# RGB_HDMI.net
KiCad netlist of a schematic drawn in EAGLE
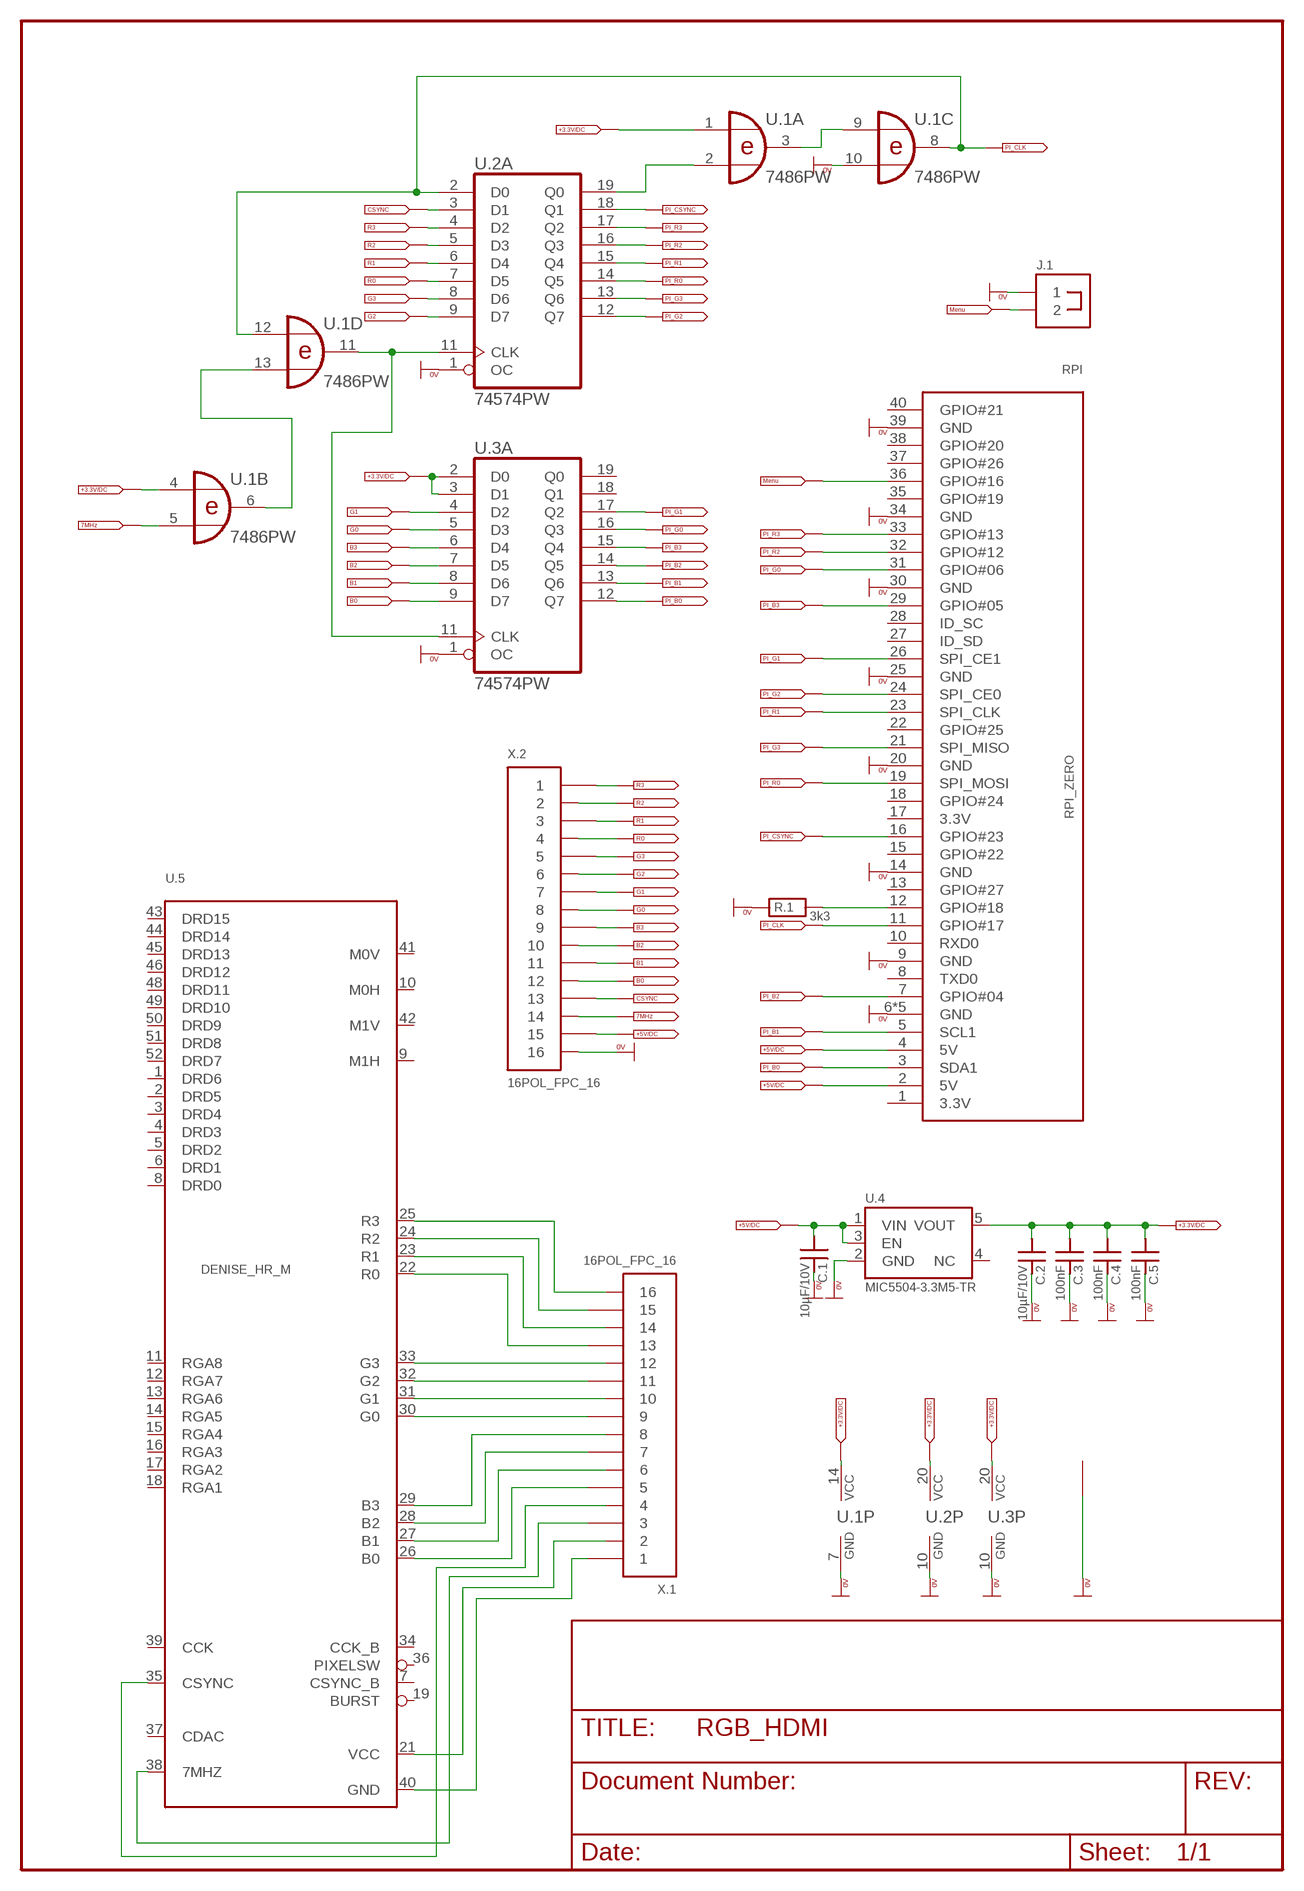
[diagram p0: schematic, sheet 1]

(export (version "E")
  (design (tool "Eeschema 10.0.6"))
  (components
    (comp (ref "C.1")
      (value "10µF/10V")
      (footprint "eagle-import:0805")
      (libsource (lib "eagle-import") (part "CAPACITOR_SMD_0805"))
    )
    (comp (ref "C.2")
      (value "10µF/10V")
      (footprint "eagle-import:0805")
      (libsource (lib "eagle-import") (part "CAPACITOR_SMD_0805"))
    )
    (comp (ref "C.3")
      (value "100nF")
      (footprint "eagle-import:0805")
      (libsource (lib "eagle-import") (part "CAPACITOR_SMD_0805"))
    )
    (comp (ref "C.4")
      (value "100nF")
      (footprint "eagle-import:0805")
      (libsource (lib "eagle-import") (part "CAPACITOR_SMD_0805"))
    )
    (comp (ref "C.5")
      (value "100nF")
      (footprint "eagle-import:0805")
      (libsource (lib "eagle-import") (part "CAPACITOR_SMD_0805"))
    )
    (comp (ref "J.1")
      (value "2POLIG_1REIHIG")
      (footprint "eagle-import:2POLIG_1REIHIG")
      (libsource (lib "eagle-import") (part "2POLIG_1REIHIG"))
    )
    (comp (ref "K.1")
      (value "PAD_1,0SQ")
      (footprint "eagle-import:1,0SQ")
      (libsource (lib "eagle-import") (part "PAD_1,0SQ"))
    )
    (comp (ref "R.1")
      (value "3k3")
      (footprint "eagle-import:0805")
      (libsource (lib "eagle-import") (part "RESISTOR_SMD_0805"))
    )
    (comp (ref "RPI")
      (value "RPI_ZERO")
      (footprint "eagle-import:RPI_ZERO_FULL")
      (libsource (lib "eagle-import") (part "RPI_ZERO"))
    )
    (comp (ref "U.1")
      (value "7486PW")
      (footprint "eagle-import:TSSOP14")
      (libsource (lib "eagle-import") (part "7486PW"))
    )
    (comp (ref "U.2")
      (value "74574PW")
      (footprint "eagle-import:TSSOP20")
      (libsource (lib "eagle-import") (part "74574PW"))
    )
    (comp (ref "U.3")
      (value "74574PW")
      (footprint "eagle-import:TSSOP20")
      (libsource (lib "eagle-import") (part "74574PW"))
    )
    (comp (ref "U.4")
      (value "MIC5504-3.3M5-TR")
      (footprint "eagle-import:SOT23-5")
      (libsource (lib "eagle-import") (part "TLV755P"))
    )
    (comp (ref "U.5")
      (value "DENISE_HR_M")
      (footprint "eagle-import:PLCC_52_MIRROR")
      (libsource (lib "eagle-import") (part "DENISE_HR_M"))
    )
    (comp (ref "X.1")
      (value "16POL_FPC_16")
      (footprint "eagle-import:MOLEX_FPC_16")
      (libsource (lib "eagle-import") (part "16POL_FPC_16"))
    )
    (comp (ref "X.2")
      (value "16POL_FPC_16")
      (footprint "eagle-import:MOLEX_FPC_16")
      (libsource (lib "eagle-import") (part "16POL_FPC_16"))
    )
  )
  (nets
    (net (code "1") (name "+3.3V-IN") (class "Default")
      (node (ref "C.2") (pin "1") (pinfunction "1_1") (pintype "passive"))
      (node (ref "C.3") (pin "1") (pinfunction "1_1") (pintype "passive"))
      (node (ref "C.4") (pin "1") (pinfunction "1_1") (pintype "passive"))
      (node (ref "C.5") (pin "1") (pinfunction "1_1") (pintype "passive"))
      (node (ref "U.1") (pin "1") (pinfunction "I0_1") (pintype "input"))
      (node (ref "U.1") (pin "14") (pinfunction "VCC_14") (pintype "power_in"))
      (node (ref "U.1") (pin "4") (pinfunction "I0_4") (pintype "input"))
      (node (ref "U.2") (pin "20") (pinfunction "VCC_20") (pintype "power_in"))
      (node (ref "U.3") (pin "2") (pinfunction "D0_2") (pintype "input"))
      (node (ref "U.3") (pin "20") (pinfunction "VCC_20") (pintype "power_in"))
      (node (ref "U.3") (pin "3") (pinfunction "D1_3") (pintype "input"))
      (node (ref "U.4") (pin "5") (pinfunction "VOUT_5") (pintype "bidirectional"))
    )
    (net (code "2") (name "+5V-IN") (class "Default")
      (node (ref "C.1") (pin "1") (pinfunction "1_1") (pintype "passive"))
      (node (ref "RPI") (pin "2") (pinfunction "5V_2") (pintype "bidirectional"))
      (node (ref "RPI") (pin "4") (pinfunction "5V_4") (pintype "bidirectional"))
      (node (ref "U.4") (pin "1") (pinfunction "VIN_1") (pintype "bidirectional"))
      (node (ref "U.4") (pin "3") (pinfunction "EN_3") (pintype "bidirectional"))
      (node (ref "X.2") (pin "15") (pinfunction "15_15") (pintype "passive"))
    )
    (net (code "3") (name "0V") (class "Default")
      (node (ref "C.1") (pin "2") (pinfunction "2_2") (pintype "passive"))
      (node (ref "C.2") (pin "2") (pinfunction "2_2") (pintype "passive"))
      (node (ref "C.3") (pin "2") (pinfunction "2_2") (pintype "passive"))
      (node (ref "C.4") (pin "2") (pinfunction "2_2") (pintype "passive"))
      (node (ref "C.5") (pin "2") (pinfunction "2_2") (pintype "passive"))
      (node (ref "J.1") (pin "1") (pinfunction "1_1") (pintype "passive"))
      (node (ref "K.1") (pin "P$1") (pinfunction "P$1_P$1") (pintype "bidirectional"))
      (node (ref "R.1") (pin "1") (pinfunction "1_1") (pintype "passive"))
      (node (ref "RPI") (pin "14") (pinfunction "GND_14") (pintype "bidirectional"))
      (node (ref "RPI") (pin "20") (pinfunction "GND_20") (pintype "bidirectional"))
      (node (ref "RPI") (pin "25") (pinfunction "GND_25") (pintype "bidirectional"))
      (node (ref "RPI") (pin "30") (pinfunction "GND_30") (pintype "bidirectional"))
      (node (ref "RPI") (pin "34") (pinfunction "GND_34") (pintype "bidirectional"))
      (node (ref "RPI") (pin "39") (pinfunction "GND_39") (pintype "bidirectional"))
      (node (ref "RPI") (pin "6") (pinfunction "GND_6") (pintype "bidirectional"))
      (node (ref "RPI") (pin "9") (pinfunction "GND_9") (pintype "bidirectional"))
      (node (ref "RPI") (pin "P$1") (pinfunction "GND_P$1") (pintype "bidirectional"))
      (node (ref "RPI") (pin "P$2") (pinfunction "GND_P$2") (pintype "bidirectional"))
      (node (ref "RPI") (pin "P$3") (pinfunction "GND_P$3") (pintype "bidirectional"))
      (node (ref "RPI") (pin "P$4") (pinfunction "GND_P$4") (pintype "bidirectional"))
      (node (ref "U.1") (pin "10") (pinfunction "I1_10") (pintype "input"))
      (node (ref "U.1") (pin "7") (pinfunction "GND_7") (pintype "power_in"))
      (node (ref "U.2") (pin "1") (pinfunction "OC_1") (pintype "input"))
      (node (ref "U.2") (pin "10") (pinfunction "GND_10") (pintype "power_in"))
      (node (ref "U.3") (pin "1") (pinfunction "OC_1") (pintype "input"))
      (node (ref "U.3") (pin "10") (pinfunction "GND_10") (pintype "power_in"))
      (node (ref "U.4") (pin "2") (pinfunction "GND_2") (pintype "bidirectional"))
      (node (ref "X.2") (pin "16") (pinfunction "16_16") (pintype "passive"))
    )
    (net (code "4") (name "7MHz") (class "Default")
      (node (ref "U.1") (pin "5") (pinfunction "I1_5") (pintype "input"))
      (node (ref "X.2") (pin "14") (pinfunction "14_14") (pintype "passive"))
    )
    (net (code "5") (name "B0") (class "Default")
      (node (ref "U.3") (pin "9") (pinfunction "D7_9") (pintype "input"))
      (node (ref "X.2") (pin "12") (pinfunction "12_12") (pintype "passive"))
    )
    (net (code "6") (name "B1") (class "Default")
      (node (ref "U.3") (pin "8") (pinfunction "D6_8") (pintype "input"))
      (node (ref "X.2") (pin "11") (pinfunction "11_11") (pintype "passive"))
    )
    (net (code "7") (name "B2") (class "Default")
      (node (ref "U.3") (pin "7") (pinfunction "D5_7") (pintype "input"))
      (node (ref "X.2") (pin "10") (pinfunction "10_10") (pintype "passive"))
    )
    (net (code "8") (name "B3") (class "Default")
      (node (ref "U.3") (pin "6") (pinfunction "D4_6") (pintype "input"))
      (node (ref "X.2") (pin "9") (pinfunction "9_9") (pintype "passive"))
    )
    (net (code "9") (name "CSYNC") (class "Default")
      (node (ref "U.2") (pin "3") (pinfunction "D1_3") (pintype "input"))
      (node (ref "X.2") (pin "13") (pinfunction "13_13") (pintype "passive"))
    )
    (net (code "10") (name "G0") (class "Default")
      (node (ref "U.3") (pin "5") (pinfunction "D3_5") (pintype "input"))
      (node (ref "X.2") (pin "8") (pinfunction "8_8") (pintype "passive"))
    )
    (net (code "11") (name "G1") (class "Default")
      (node (ref "U.3") (pin "4") (pinfunction "D2_4") (pintype "input"))
      (node (ref "X.2") (pin "7") (pinfunction "7_7") (pintype "passive"))
    )
    (net (code "12") (name "G2") (class "Default")
      (node (ref "U.2") (pin "9") (pinfunction "D7_9") (pintype "input"))
      (node (ref "X.2") (pin "6") (pinfunction "6_6") (pintype "passive"))
    )
    (net (code "13") (name "G3") (class "Default")
      (node (ref "U.2") (pin "8") (pinfunction "D6_8") (pintype "input"))
      (node (ref "X.2") (pin "5") (pinfunction "5_5") (pintype "passive"))
    )
    (net (code "14") (name "Menu") (class "Default")
      (node (ref "J.1") (pin "2") (pinfunction "2_2") (pintype "passive"))
      (node (ref "RPI") (pin "36") (pinfunction "GPIO#16_36") (pintype "bidirectional"))
    )
    (net (code "15") (name "Net-(RPI-GPIO#18)") (class "Default")
      (node (ref "R.1") (pin "2") (pinfunction "2_2") (pintype "passive"))
      (node (ref "RPI") (pin "12") (pinfunction "GPIO#18_12") (pintype "bidirectional"))
    )
    (net (code "16") (name "Net-(U.1A-I1)") (class "Default")
      (node (ref "U.1") (pin "2") (pinfunction "I1_2") (pintype "input"))
      (node (ref "U.2") (pin "19") (pinfunction "Q0_19") (pintype "tri_state"))
    )
    (net (code "17") (name "Net-(U.1A-O)") (class "Default")
      (node (ref "U.1") (pin "3") (pinfunction "O_3") (pintype "output"))
      (node (ref "U.1") (pin "9") (pinfunction "I0_9") (pintype "input"))
    )
    (net (code "18") (name "Net-(U.1B-O)") (class "Default")
      (node (ref "U.1") (pin "13") (pinfunction "I1_13") (pintype "input"))
      (node (ref "U.1") (pin "6") (pinfunction "O_6") (pintype "output"))
    )
    (net (code "19") (name "Net-(U.1D-O)") (class "Default")
      (node (ref "U.1") (pin "11") (pinfunction "O_11") (pintype "output"))
      (node (ref "U.2") (pin "11") (pinfunction "CLK_11") (pintype "input"))
      (node (ref "U.3") (pin "11") (pinfunction "CLK_11") (pintype "input"))
    )
    (net (code "20") (name "Net-(U.5-7MHZ)") (class "Default")
      (node (ref "U.5") (pin "38") (pinfunction "7MHZ_38") (pintype "bidirectional"))
      (node (ref "X.1") (pin "3") (pinfunction "3_3") (pintype "passive"))
    )
    (net (code "21") (name "Net-(U.5-B0)") (class "Default")
      (node (ref "U.5") (pin "26") (pinfunction "B0_26") (pintype "bidirectional"))
      (node (ref "X.1") (pin "5") (pinfunction "5_5") (pintype "passive"))
    )
    (net (code "22") (name "Net-(U.5-B1)") (class "Default")
      (node (ref "U.5") (pin "27") (pinfunction "B1_27") (pintype "bidirectional"))
      (node (ref "X.1") (pin "6") (pinfunction "6_6") (pintype "passive"))
    )
    (net (code "23") (name "Net-(U.5-B2)") (class "Default")
      (node (ref "U.5") (pin "28") (pinfunction "B2_28") (pintype "bidirectional"))
      (node (ref "X.1") (pin "7") (pinfunction "7_7") (pintype "passive"))
    )
    (net (code "24") (name "Net-(U.5-B3)") (class "Default")
      (node (ref "U.5") (pin "29") (pinfunction "B3_29") (pintype "bidirectional"))
      (node (ref "X.1") (pin "8") (pinfunction "8_8") (pintype "passive"))
    )
    (net (code "25") (name "Net-(U.5-CSYNC)") (class "Default")
      (node (ref "U.5") (pin "35") (pinfunction "CSYNC_35") (pintype "bidirectional"))
      (node (ref "X.1") (pin "4") (pinfunction "4_4") (pintype "passive"))
    )
    (net (code "26") (name "Net-(U.5-G0)") (class "Default")
      (node (ref "U.5") (pin "30") (pinfunction "G0_30") (pintype "bidirectional"))
      (node (ref "X.1") (pin "9") (pinfunction "9_9") (pintype "passive"))
    )
    (net (code "27") (name "Net-(U.5-G1)") (class "Default")
      (node (ref "U.5") (pin "31") (pinfunction "G1_31") (pintype "bidirectional"))
      (node (ref "X.1") (pin "10") (pinfunction "10_10") (pintype "passive"))
    )
    (net (code "28") (name "Net-(U.5-G2)") (class "Default")
      (node (ref "U.5") (pin "32") (pinfunction "G2_32") (pintype "bidirectional"))
      (node (ref "X.1") (pin "11") (pinfunction "11_11") (pintype "passive"))
    )
    (net (code "29") (name "Net-(U.5-G3)") (class "Default")
      (node (ref "U.5") (pin "33") (pinfunction "G3_33") (pintype "bidirectional"))
      (node (ref "X.1") (pin "12") (pinfunction "12_12") (pintype "passive"))
    )
    (net (code "30") (name "Net-(U.5-GND)") (class "Default")
      (node (ref "U.5") (pin "40") (pinfunction "GND_40") (pintype "bidirectional"))
      (node (ref "X.1") (pin "1") (pinfunction "1_1") (pintype "passive"))
    )
    (net (code "31") (name "Net-(U.5-R0)") (class "Default")
      (node (ref "U.5") (pin "22") (pinfunction "R0_22") (pintype "bidirectional"))
      (node (ref "X.1") (pin "13") (pinfunction "13_13") (pintype "passive"))
    )
    (net (code "32") (name "Net-(U.5-R1)") (class "Default")
      (node (ref "U.5") (pin "23") (pinfunction "R1_23") (pintype "bidirectional"))
      (node (ref "X.1") (pin "14") (pinfunction "14_14") (pintype "passive"))
    )
    (net (code "33") (name "Net-(U.5-R2)") (class "Default")
      (node (ref "U.5") (pin "24") (pinfunction "R2_24") (pintype "bidirectional"))
      (node (ref "X.1") (pin "15") (pinfunction "15_15") (pintype "passive"))
    )
    (net (code "34") (name "Net-(U.5-R3)") (class "Default")
      (node (ref "U.5") (pin "25") (pinfunction "R3_25") (pintype "bidirectional"))
      (node (ref "X.1") (pin "16") (pinfunction "16_16") (pintype "passive"))
    )
    (net (code "35") (name "Net-(U.5-VCC)") (class "Default")
      (node (ref "U.5") (pin "21") (pinfunction "VCC_21") (pintype "bidirectional"))
      (node (ref "X.1") (pin "2") (pinfunction "2_2") (pintype "passive"))
    )
    (net (code "36") (name "PI_B0") (class "Default")
      (node (ref "RPI") (pin "3") (pinfunction "SDA1_3") (pintype "bidirectional"))
      (node (ref "U.3") (pin "12") (pinfunction "Q7_12") (pintype "tri_state"))
    )
    (net (code "37") (name "PI_B1") (class "Default")
      (node (ref "RPI") (pin "5") (pinfunction "SCL1_5") (pintype "bidirectional"))
      (node (ref "U.3") (pin "13") (pinfunction "Q6_13") (pintype "tri_state"))
    )
    (net (code "38") (name "PI_B2") (class "Default")
      (node (ref "RPI") (pin "7") (pinfunction "GPIO#04_7") (pintype "bidirectional"))
      (node (ref "U.3") (pin "14") (pinfunction "Q5_14") (pintype "tri_state"))
    )
    (net (code "39") (name "PI_B3") (class "Default")
      (node (ref "RPI") (pin "29") (pinfunction "GPIO#05_29") (pintype "bidirectional"))
      (node (ref "U.3") (pin "15") (pinfunction "Q4_15") (pintype "tri_state"))
    )
    (net (code "40") (name "PI_CLK") (class "Default")
      (node (ref "RPI") (pin "11") (pinfunction "GPIO#17_11") (pintype "bidirectional"))
      (node (ref "U.1") (pin "12") (pinfunction "I0_12") (pintype "input"))
      (node (ref "U.1") (pin "8") (pinfunction "O_8") (pintype "output"))
      (node (ref "U.2") (pin "2") (pinfunction "D0_2") (pintype "input"))
    )
    (net (code "41") (name "PI_CSYNC") (class "Default")
      (node (ref "RPI") (pin "16") (pinfunction "GPIO#23_16") (pintype "bidirectional"))
      (node (ref "U.2") (pin "18") (pinfunction "Q1_18") (pintype "tri_state"))
    )
    (net (code "42") (name "PI_G0") (class "Default")
      (node (ref "RPI") (pin "31") (pinfunction "GPIO#06_31") (pintype "bidirectional"))
      (node (ref "U.3") (pin "16") (pinfunction "Q3_16") (pintype "tri_state"))
    )
    (net (code "43") (name "PI_G1") (class "Default")
      (node (ref "RPI") (pin "26") (pinfunction "SPI_CE1_26") (pintype "bidirectional"))
      (node (ref "U.3") (pin "17") (pinfunction "Q2_17") (pintype "tri_state"))
    )
    (net (code "44") (name "PI_G2") (class "Default")
      (node (ref "RPI") (pin "24") (pinfunction "SPI_CE0_24") (pintype "bidirectional"))
      (node (ref "U.2") (pin "12") (pinfunction "Q7_12") (pintype "tri_state"))
    )
    (net (code "45") (name "PI_G3") (class "Default")
      (node (ref "RPI") (pin "21") (pinfunction "SPI_MISO_21") (pintype "bidirectional"))
      (node (ref "U.2") (pin "13") (pinfunction "Q6_13") (pintype "tri_state"))
    )
    (net (code "46") (name "PI_R0") (class "Default")
      (node (ref "RPI") (pin "19") (pinfunction "SPI_MOSI_19") (pintype "bidirectional"))
      (node (ref "U.2") (pin "14") (pinfunction "Q5_14") (pintype "tri_state"))
    )
    (net (code "47") (name "PI_R1") (class "Default")
      (node (ref "RPI") (pin "23") (pinfunction "SPI_CLK_23") (pintype "bidirectional"))
      (node (ref "U.2") (pin "15") (pinfunction "Q4_15") (pintype "tri_state"))
    )
    (net (code "48") (name "PI_R2") (class "Default")
      (node (ref "RPI") (pin "32") (pinfunction "GPIO#12_32") (pintype "bidirectional"))
      (node (ref "U.2") (pin "16") (pinfunction "Q3_16") (pintype "tri_state"))
    )
    (net (code "49") (name "PI_R3") (class "Default")
      (node (ref "RPI") (pin "33") (pinfunction "GPIO#13_33") (pintype "bidirectional"))
      (node (ref "U.2") (pin "17") (pinfunction "Q2_17") (pintype "tri_state"))
    )
    (net (code "50") (name "R0") (class "Default")
      (node (ref "U.2") (pin "7") (pinfunction "D5_7") (pintype "input"))
      (node (ref "X.2") (pin "4") (pinfunction "4_4") (pintype "passive"))
    )
    (net (code "51") (name "R1") (class "Default")
      (node (ref "U.2") (pin "6") (pinfunction "D4_6") (pintype "input"))
      (node (ref "X.2") (pin "3") (pinfunction "3_3") (pintype "passive"))
    )
    (net (code "52") (name "R2") (class "Default")
      (node (ref "U.2") (pin "5") (pinfunction "D3_5") (pintype "input"))
      (node (ref "X.2") (pin "2") (pinfunction "2_2") (pintype "passive"))
    )
    (net (code "53") (name "R3") (class "Default")
      (node (ref "U.2") (pin "4") (pinfunction "D2_4") (pintype "input"))
      (node (ref "X.2") (pin "1") (pinfunction "1_1") (pintype "passive"))
    )
    (net (code "54") (name "unconnected-(RPI-3.3V-Pad1)") (class "Default")
      (node (ref "RPI") (pin "1") (pinfunction "3.3V_1") (pintype "bidirectional"))
    )
    (net (code "55") (name "unconnected-(RPI-3.3V-Pad17)") (class "Default")
      (node (ref "RPI") (pin "17") (pinfunction "3.3V_17") (pintype "bidirectional"))
    )
    (net (code "56") (name "unconnected-(RPI-GPIO#19-Pad35)") (class "Default")
      (node (ref "RPI") (pin "35") (pinfunction "GPIO#19_35") (pintype "bidirectional"))
    )
    (net (code "57") (name "unconnected-(RPI-GPIO#20-Pad38)") (class "Default")
      (node (ref "RPI") (pin "38") (pinfunction "GPIO#20_38") (pintype "bidirectional"))
    )
    (net (code "58") (name "unconnected-(RPI-GPIO#21-Pad40)") (class "Default")
      (node (ref "RPI") (pin "40") (pinfunction "GPIO#21_40") (pintype "bidirectional"))
    )
    (net (code "59") (name "unconnected-(RPI-GPIO#22-Pad15)") (class "Default")
      (node (ref "RPI") (pin "15") (pinfunction "GPIO#22_15") (pintype "bidirectional"))
    )
    (net (code "60") (name "unconnected-(RPI-GPIO#24-Pad18)") (class "Default")
      (node (ref "RPI") (pin "18") (pinfunction "GPIO#24_18") (pintype "bidirectional"))
    )
    (net (code "61") (name "unconnected-(RPI-GPIO#25-Pad22)") (class "Default")
      (node (ref "RPI") (pin "22") (pinfunction "GPIO#25_22") (pintype "bidirectional"))
    )
    (net (code "62") (name "unconnected-(RPI-GPIO#26-Pad37)") (class "Default")
      (node (ref "RPI") (pin "37") (pinfunction "GPIO#26_37") (pintype "bidirectional"))
    )
    (net (code "63") (name "unconnected-(RPI-GPIO#27-Pad13)") (class "Default")
      (node (ref "RPI") (pin "13") (pinfunction "GPIO#27_13") (pintype "bidirectional"))
    )
    (net (code "64") (name "unconnected-(RPI-ID_SC-Pad28)") (class "Default")
      (node (ref "RPI") (pin "28") (pinfunction "ID_SC_28") (pintype "bidirectional"))
    )
    (net (code "65") (name "unconnected-(RPI-ID_SD-Pad27)") (class "Default")
      (node (ref "RPI") (pin "27") (pinfunction "ID_SD_27") (pintype "bidirectional"))
    )
    (net (code "66") (name "unconnected-(RPI-RXD0-Pad10)") (class "Default")
      (node (ref "RPI") (pin "10") (pinfunction "RXD0_10") (pintype "bidirectional"))
    )
    (net (code "67") (name "unconnected-(RPI-TXD0-Pad8)") (class "Default")
      (node (ref "RPI") (pin "8") (pinfunction "TXD0_8") (pintype "bidirectional"))
    )
    (net (code "68") (name "unconnected-(U.3A-Q0-Pad19)") (class "Default")
      (node (ref "U.3") (pin "19") (pinfunction "Q0_19") (pintype "tri_state"))
    )
    (net (code "69") (name "unconnected-(U.3A-Q1-Pad18)") (class "Default")
      (node (ref "U.3") (pin "18") (pinfunction "Q1_18") (pintype "tri_state"))
    )
    (net (code "70") (name "unconnected-(U.4-NC-Pad4)") (class "Default")
      (node (ref "U.4") (pin "4") (pinfunction "NC_4") (pintype "bidirectional"))
    )
    (net (code "71") (name "unconnected-(U.5-BURST-Pad19)") (class "Default")
      (node (ref "U.5") (pin "19") (pinfunction "BURST_19") (pintype "bidirectional"))
    )
    (net (code "72") (name "unconnected-(U.5-CCK-Pad39)") (class "Default")
      (node (ref "U.5") (pin "39") (pinfunction "CCK_39") (pintype "bidirectional"))
    )
    (net (code "73") (name "unconnected-(U.5-CCK_B-Pad34)") (class "Default")
      (node (ref "U.5") (pin "34") (pinfunction "CCK_B_34") (pintype "bidirectional"))
    )
    (net (code "74") (name "unconnected-(U.5-CDAC-Pad37)") (class "Default")
      (node (ref "U.5") (pin "37") (pinfunction "CDAC_37") (pintype "bidirectional"))
    )
    (net (code "75") (name "unconnected-(U.5-CSYNC_B-Pad7)") (class "Default")
      (node (ref "U.5") (pin "7") (pinfunction "CSYNC_B_7") (pintype "bidirectional"))
    )
    (net (code "76") (name "unconnected-(U.5-DRD0-Pad8)") (class "Default")
      (node (ref "U.5") (pin "8") (pinfunction "DRD0_8") (pintype "bidirectional"))
    )
    (net (code "77") (name "unconnected-(U.5-DRD1-Pad6)") (class "Default")
      (node (ref "U.5") (pin "6") (pinfunction "DRD1_6") (pintype "bidirectional"))
    )
    (net (code "78") (name "unconnected-(U.5-DRD2-Pad5)") (class "Default")
      (node (ref "U.5") (pin "5") (pinfunction "DRD2_5") (pintype "bidirectional"))
    )
    (net (code "79") (name "unconnected-(U.5-DRD3-Pad4)") (class "Default")
      (node (ref "U.5") (pin "4") (pinfunction "DRD3_4") (pintype "bidirectional"))
    )
    (net (code "80") (name "unconnected-(U.5-DRD4-Pad3)") (class "Default")
      (node (ref "U.5") (pin "3") (pinfunction "DRD4_3") (pintype "bidirectional"))
    )
    (net (code "81") (name "unconnected-(U.5-DRD5-Pad2)") (class "Default")
      (node (ref "U.5") (pin "2") (pinfunction "DRD5_2") (pintype "bidirectional"))
    )
    (net (code "82") (name "unconnected-(U.5-DRD6-Pad1)") (class "Default")
      (node (ref "U.5") (pin "1") (pinfunction "DRD6_1") (pintype "bidirectional"))
    )
    (net (code "83") (name "unconnected-(U.5-DRD7-Pad52)") (class "Default")
      (node (ref "U.5") (pin "52") (pinfunction "DRD7_52") (pintype "bidirectional"))
    )
    (net (code "84") (name "unconnected-(U.5-DRD8-Pad51)") (class "Default")
      (node (ref "U.5") (pin "51") (pinfunction "DRD8_51") (pintype "bidirectional"))
    )
    (net (code "85") (name "unconnected-(U.5-DRD9-Pad50)") (class "Default")
      (node (ref "U.5") (pin "50") (pinfunction "DRD9_50") (pintype "bidirectional"))
    )
    (net (code "86") (name "unconnected-(U.5-DRD10-Pad49)") (class "Default")
      (node (ref "U.5") (pin "49") (pinfunction "DRD10_49") (pintype "bidirectional"))
    )
    (net (code "87") (name "unconnected-(U.5-DRD11-Pad48)") (class "Default")
      (node (ref "U.5") (pin "48") (pinfunction "DRD11_48") (pintype "bidirectional"))
    )
    (net (code "88") (name "unconnected-(U.5-DRD12-Pad46)") (class "Default")
      (node (ref "U.5") (pin "46") (pinfunction "DRD12_46") (pintype "bidirectional"))
    )
    (net (code "89") (name "unconnected-(U.5-DRD13-Pad45)") (class "Default")
      (node (ref "U.5") (pin "45") (pinfunction "DRD13_45") (pintype "bidirectional"))
    )
    (net (code "90") (name "unconnected-(U.5-DRD14-Pad44)") (class "Default")
      (node (ref "U.5") (pin "44") (pinfunction "DRD14_44") (pintype "bidirectional"))
    )
    (net (code "91") (name "unconnected-(U.5-DRD15-Pad43)") (class "Default")
      (node (ref "U.5") (pin "43") (pinfunction "DRD15_43") (pintype "bidirectional"))
    )
    (net (code "92") (name "unconnected-(U.5-M0H-Pad10)") (class "Default")
      (node (ref "U.5") (pin "10") (pinfunction "M0H_10") (pintype "bidirectional"))
    )
    (net (code "93") (name "unconnected-(U.5-M0V-Pad41)") (class "Default")
      (node (ref "U.5") (pin "41") (pinfunction "M0V_41") (pintype "bidirectional"))
    )
    (net (code "94") (name "unconnected-(U.5-M1H-Pad9)") (class "Default")
      (node (ref "U.5") (pin "9") (pinfunction "M1H_9") (pintype "bidirectional"))
    )
    (net (code "95") (name "unconnected-(U.5-M1V-Pad42)") (class "Default")
      (node (ref "U.5") (pin "42") (pinfunction "M1V_42") (pintype "bidirectional"))
    )
    (net (code "96") (name "unconnected-(U.5-PIXELSW-Pad36)") (class "Default")
      (node (ref "U.5") (pin "36") (pinfunction "PIXELSW_36") (pintype "bidirectional"))
    )
    (net (code "97") (name "unconnected-(U.5-RGA1-Pad18)") (class "Default")
      (node (ref "U.5") (pin "18") (pinfunction "RGA1_18") (pintype "bidirectional"))
    )
    (net (code "98") (name "unconnected-(U.5-RGA2-Pad17)") (class "Default")
      (node (ref "U.5") (pin "17") (pinfunction "RGA2_17") (pintype "bidirectional"))
    )
    (net (code "99") (name "unconnected-(U.5-RGA3-Pad16)") (class "Default")
      (node (ref "U.5") (pin "16") (pinfunction "RGA3_16") (pintype "bidirectional"))
    )
    (net (code "100") (name "unconnected-(U.5-RGA4-Pad15)") (class "Default")
      (node (ref "U.5") (pin "15") (pinfunction "RGA4_15") (pintype "bidirectional"))
    )
    (net (code "101") (name "unconnected-(U.5-RGA5-Pad14)") (class "Default")
      (node (ref "U.5") (pin "14") (pinfunction "RGA5_14") (pintype "bidirectional"))
    )
    (net (code "102") (name "unconnected-(U.5-RGA6-Pad13)") (class "Default")
      (node (ref "U.5") (pin "13") (pinfunction "RGA6_13") (pintype "bidirectional"))
    )
    (net (code "103") (name "unconnected-(U.5-RGA7-Pad12)") (class "Default")
      (node (ref "U.5") (pin "12") (pinfunction "RGA7_12") (pintype "bidirectional"))
    )
    (net (code "104") (name "unconnected-(U.5-RGA8-Pad11)") (class "Default")
      (node (ref "U.5") (pin "11") (pinfunction "RGA8_11") (pintype "bidirectional"))
    )
  )
)
